# medidor_nao_invasivo.net
KiCad netlist of a schematic drawn in EAGLE
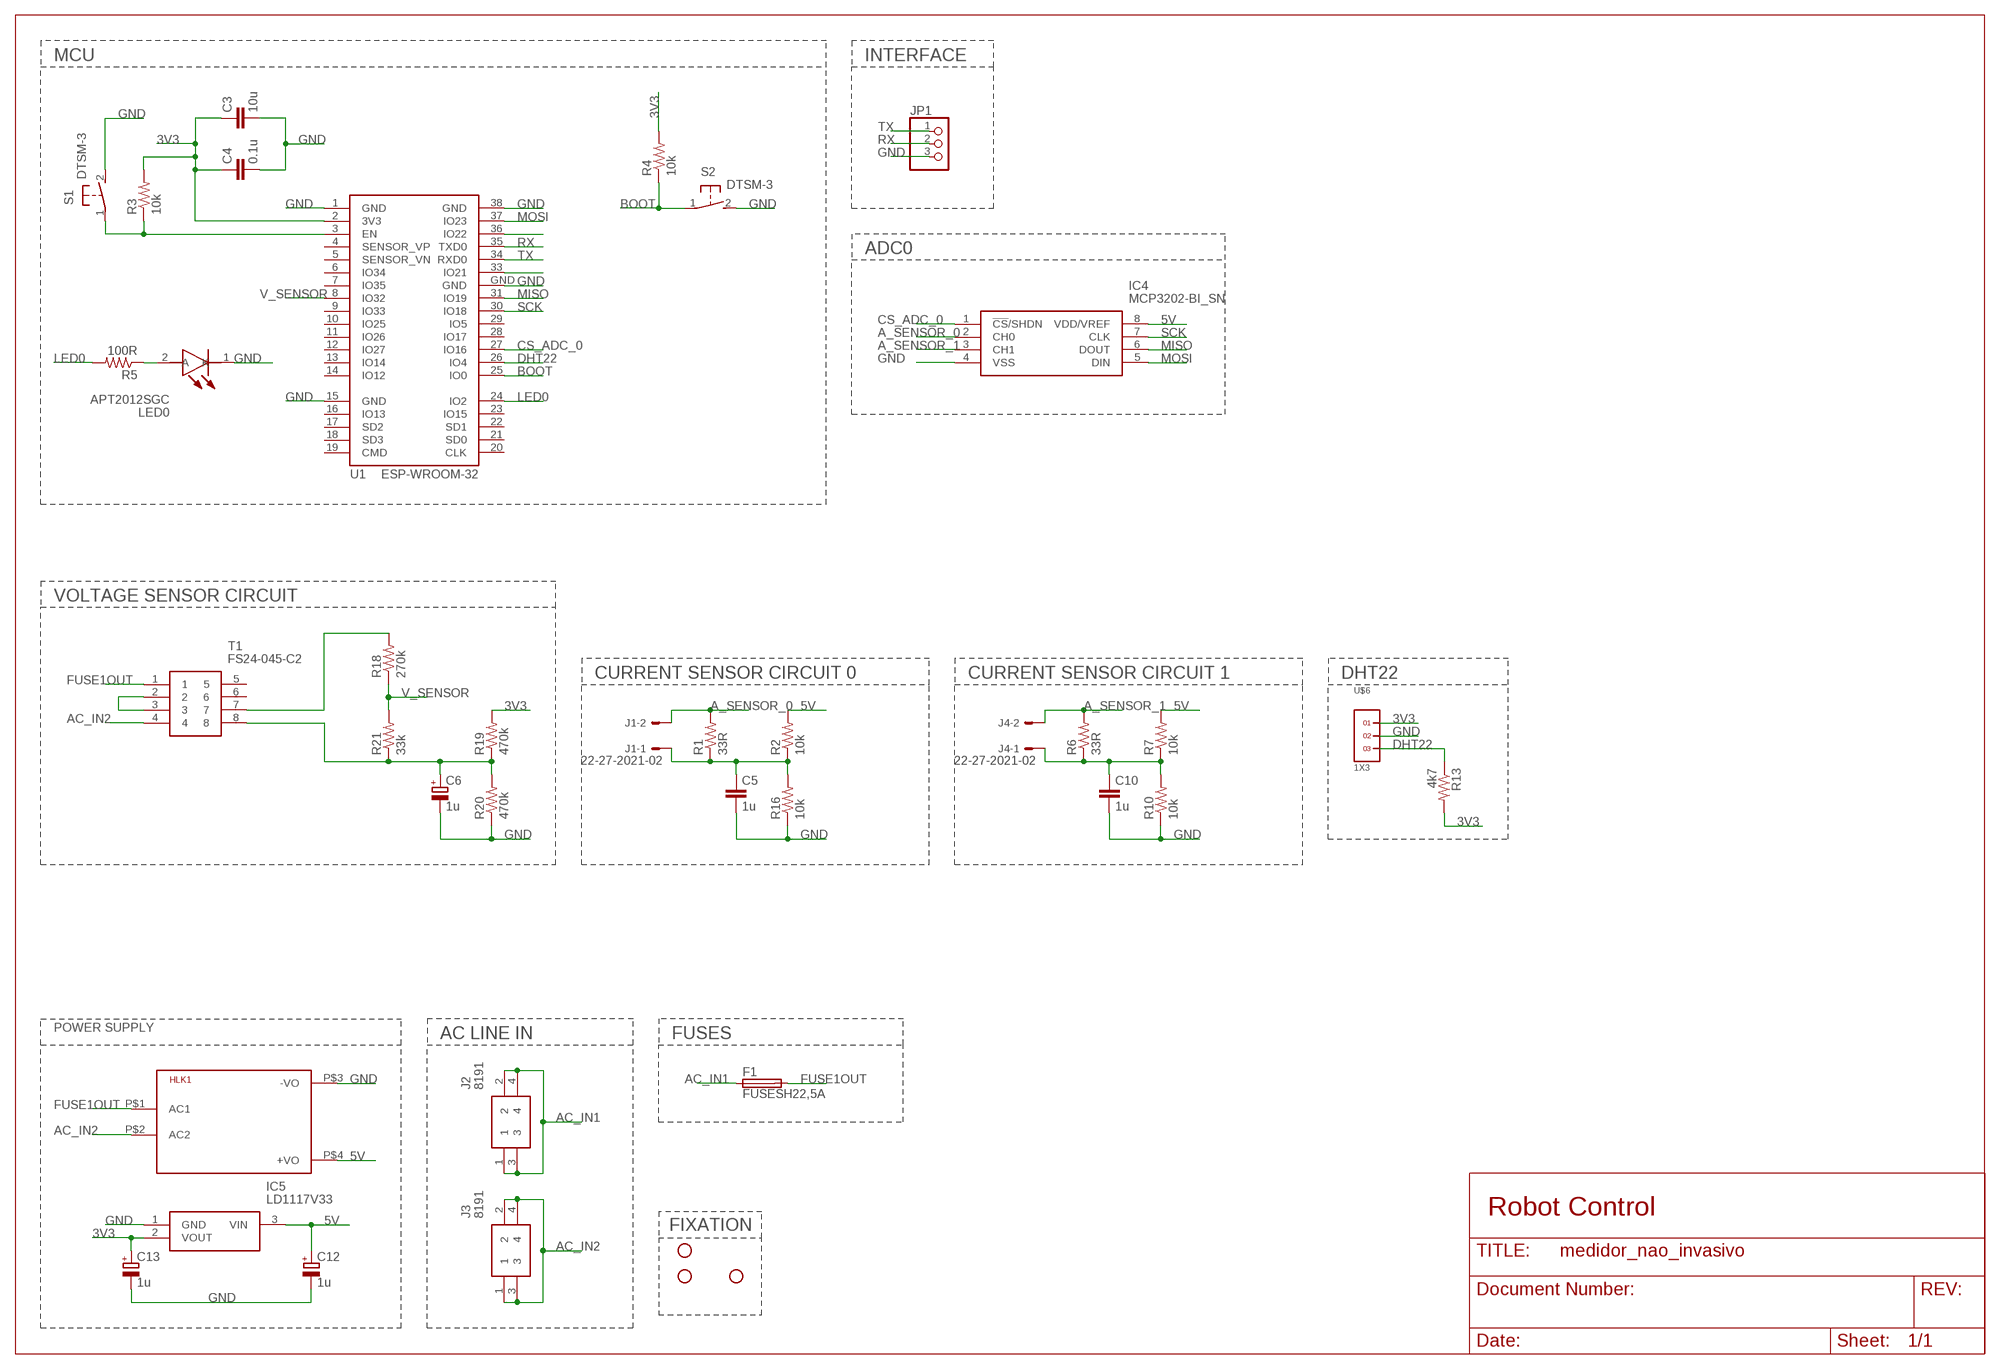
[diagram p0: schematic, sheet 1]

(export (version "E")
  (design (tool "Eeschema 10.0.6"))
  (components
    (comp (ref "C3")
      (value "10u")
      (footprint "eagle-import:C0805")
      (libsource (lib "eagle-import") (part "C-EUC0805"))
    )
    (comp (ref "C4")
      (value "0.1u")
      (footprint "eagle-import:C0805")
      (libsource (lib "eagle-import") (part "C-EUC0805"))
    )
    (comp (ref "C5")
      (value "1u")
      (footprint "eagle-import:C0805")
      (libsource (lib "eagle-import") (part "C-EUC0805"))
    )
    (comp (ref "C6")
      (value "1u")
      (footprint "eagle-import:E1,8-4")
      (libsource (lib "eagle-import") (part "CPOL-EUE1.8-4"))
    )
    (comp (ref "C10")
      (value "1u")
      (footprint "eagle-import:C0805")
      (libsource (lib "eagle-import") (part "C-EUC0805"))
    )
    (comp (ref "C12")
      (value "1u")
      (footprint "eagle-import:E1,8-4")
      (libsource (lib "eagle-import") (part "CPOL-EUE1.8-4"))
    )
    (comp (ref "C13")
      (value "1u")
      (footprint "eagle-import:E1,8-4")
      (libsource (lib "eagle-import") (part "CPOL-EUE1.8-4"))
    )
    (comp (ref "F1")
      (value "FUSESH22,5A")
      (footprint "eagle-import:SH22,5A")
      (libsource (lib "eagle-import") (part "FUSESH22,5A"))
    )
    (comp (ref "HLK1")
      (value "HLK-PM013W")
      (footprint "eagle-import:HLK-PM01")
      (libsource (lib "eagle-import") (part "HLK-PM013W"))
    )
    (comp (ref "IC4")
      (value "MCP3202-BI_SN")
      (footprint "eagle-import:SOIC127P600X175-8N")
      (fields
        (field (name "MANUFACTURER_PART_NUMBER") "MCP3202-BI/SN")
        (field (name "MOUSER_PART_NUMBER") "579-MCP3202BISN")
      )
      (libsource (lib "eagle-import") (part "MCP3202-BI_SN"))
    )
    (comp (ref "IC5")
      (value "LD1117V33")
      (footprint "eagle-import:TO270P460X1020X2008-3P")
      (fields (field (name "MOUSER_PART_NUMBER") "511-LD1117V33"))
      (libsource (lib "eagle-import") (part "LD1117V33"))
    )
    (comp (ref "J1")
      (value "22-27-2021-02")
      (footprint "eagle-import:6410-02")
      (fields (field (name "MF") "MOLEX"))
      (libsource (lib "eagle-import") (part "22-?-0227-2021"))
    )
    (comp (ref "J2")
      (value "8191")
      (footprint "eagle-import:8191")
      (fields (field (name "MOUSER_PART_NUMBER") "534-8191"))
      (libsource (lib "eagle-import") (part "8191"))
    )
    (comp (ref "J3")
      (value "8191")
      (footprint "eagle-import:8191")
      (fields (field (name "MOUSER_PART_NUMBER") "534-8191"))
      (libsource (lib "eagle-import") (part "8191"))
    )
    (comp (ref "J4")
      (value "22-27-2021-02")
      (footprint "eagle-import:6410-02")
      (fields (field (name "MF") "MOLEX"))
      (libsource (lib "eagle-import") (part "22-?-0227-2021"))
    )
    (comp (ref "JP1")
      (value "PINHD-1X3")
      (footprint "eagle-import:1X03")
      (libsource (lib "eagle-import") (part "PINHD-1X3"))
    )
    (comp (ref "LED0")
      (value "APT2012SGC")
      (footprint "eagle-import:LEDC2012X85N")
      (fields (field (name "MOUSER_PART_NUMBER") "604-APT2012SGC"))
      (libsource (lib "eagle-import") (part "APT2012SGC"))
    )
    (comp (ref "R1")
      (value "33R")
      (footprint "eagle-import:R0805")
      (libsource (lib "eagle-import") (part "R-US_R0805"))
    )
    (comp (ref "R2")
      (value "10k")
      (footprint "eagle-import:R0805")
      (libsource (lib "eagle-import") (part "R-US_R0805"))
    )
    (comp (ref "R3")
      (value "10k")
      (footprint "eagle-import:R0805")
      (libsource (lib "eagle-import") (part "R-US_R0805"))
    )
    (comp (ref "R4")
      (value "10k")
      (footprint "eagle-import:R0805")
      (libsource (lib "eagle-import") (part "R-US_R0805"))
    )
    (comp (ref "R5")
      (value "100R")
      (footprint "eagle-import:R0805")
      (libsource (lib "eagle-import") (part "R-US_R0805"))
    )
    (comp (ref "R6")
      (value "33R")
      (footprint "eagle-import:R0805")
      (libsource (lib "eagle-import") (part "R-US_R0805"))
    )
    (comp (ref "R7")
      (value "10k")
      (footprint "eagle-import:R0805")
      (libsource (lib "eagle-import") (part "R-US_R0805"))
    )
    (comp (ref "R10")
      (value "10k")
      (footprint "eagle-import:R0805")
      (libsource (lib "eagle-import") (part "R-US_R0805"))
    )
    (comp (ref "R13")
      (value "4k7")
      (footprint "eagle-import:R0805")
      (libsource (lib "eagle-import") (part "R-US_R0805"))
    )
    (comp (ref "R16")
      (value "10k")
      (footprint "eagle-import:R0805")
      (libsource (lib "eagle-import") (part "R-US_R0805"))
    )
    (comp (ref "R18")
      (value "270k")
      (footprint "eagle-import:AXIAL-0.3-KIT")
      (libsource (lib "eagle-import") (part "RESISTORAXIAL-0.3-KIT"))
    )
    (comp (ref "R19")
      (value "470k")
      (footprint "eagle-import:AXIAL-0.3-KIT")
      (libsource (lib "eagle-import") (part "RESISTORAXIAL-0.3-KIT"))
    )
    (comp (ref "R20")
      (value "470k")
      (footprint "eagle-import:AXIAL-0.3-KIT")
      (libsource (lib "eagle-import") (part "RESISTORAXIAL-0.3-KIT"))
    )
    (comp (ref "R21")
      (value "33k")
      (footprint "eagle-import:AXIAL-0.3-KIT")
      (libsource (lib "eagle-import") (part "RESISTORAXIAL-0.3-KIT"))
    )
    (comp (ref "S1")
      (value "DTSM-3")
      (footprint "eagle-import:DTSM-3")
      (libsource (lib "eagle-import") (part "DTSM-3"))
    )
    (comp (ref "S2")
      (value "DTSM-3")
      (footprint "eagle-import:DTSM-3")
      (libsource (lib "eagle-import") (part "DTSM-3"))
    )
    (comp (ref "STANDOFF1")
      (value "STAND-OFF")
      (footprint "eagle-import:STAND-OFF")
      (libsource (lib "eagle-import") (part "STAND-OFF"))
    )
    (comp (ref "STANDOFF2")
      (value "STAND-OFF")
      (footprint "eagle-import:STAND-OFF")
      (libsource (lib "eagle-import") (part "STAND-OFF"))
    )
    (comp (ref "STANDOFF4")
      (value "STAND-OFF")
      (footprint "eagle-import:STAND-OFF")
      (libsource (lib "eagle-import") (part "STAND-OFF"))
    )
    (comp (ref "T1")
      (value "FS24-045-C2")
      (footprint "eagle-import:FS24045C2")
      (fields (field (name "MOUSER_PART_NUMBER") "553-FS24-045-C2"))
      (libsource (lib "eagle-import") (part "FS24-045-C2"))
    )
    (comp (ref "U$6")
      (value "1X3")
      (footprint "eagle-import:1X3")
      (libsource (lib "eagle-import") (part "1X3"))
    )
    (comp (ref "U1")
      (value "ESP-WROOM-32")
      (footprint "eagle-import:ESP-WROOM-32")
      (libsource (lib "eagle-import") (part "ESP-WROOM-32"))
    )
  )
  (nets
    (net (code "1") (name "/3V3") (class "Default")
      (node (ref "C13") (pin "+") (pinfunction "+_+") (pintype "passive"))
      (node (ref "C3") (pin "1") (pinfunction "1_1") (pintype "passive"))
      (node (ref "C4") (pin "1") (pinfunction "1_1") (pintype "passive"))
      (node (ref "IC5") (pin "2") (pinfunction "VOUT_2") (pintype "output"))
      (node (ref "R13") (pin "2") (pinfunction "2_2") (pintype "passive"))
      (node (ref "R19") (pin "P$2") (pinfunction "2_P$2") (pintype "passive"))
      (node (ref "R3") (pin "2") (pinfunction "2_2") (pintype "passive"))
      (node (ref "R4") (pin "2") (pinfunction "2_2") (pintype "passive"))
      (node (ref "U$6") (pin "1") (pinfunction "1_1") (pintype "bidirectional"))
      (node (ref "U1") (pin "2") (pinfunction "3V3_2") (pintype "power_in"))
    )
    (net (code "2") (name "/5V") (class "Default")
      (node (ref "C12") (pin "+") (pinfunction "+_+") (pintype "passive"))
      (node (ref "HLK1") (pin "P$4") (pinfunction "+VO_P$4") (pintype "bidirectional"))
      (node (ref "IC4") (pin "8") (pinfunction "VDD/VREF_8") (pintype "power_in"))
      (node (ref "IC5") (pin "3") (pinfunction "VIN_3") (pintype "input"))
      (node (ref "R2") (pin "2") (pinfunction "2_2") (pintype "passive"))
      (node (ref "R7") (pin "2") (pinfunction "2_2") (pintype "passive"))
    )
    (net (code "3") (name "/AC_IN1") (class "Default")
      (node (ref "F1") (pin "1") (pinfunction "1_1") (pintype "passive"))
      (node (ref "J2") (pin "1") (pinfunction "1_1") (pintype "bidirectional"))
      (node (ref "J2") (pin "2") (pinfunction "2_2") (pintype "bidirectional"))
      (node (ref "J2") (pin "3") (pinfunction "3_3") (pintype "bidirectional"))
      (node (ref "J2") (pin "4") (pinfunction "4_4") (pintype "bidirectional"))
    )
    (net (code "4") (name "/AC_IN2") (class "Default")
      (node (ref "HLK1") (pin "P$2") (pinfunction "AC2_P$2") (pintype "bidirectional"))
      (node (ref "J3") (pin "1") (pinfunction "1_1") (pintype "bidirectional"))
      (node (ref "J3") (pin "2") (pinfunction "2_2") (pintype "bidirectional"))
      (node (ref "J3") (pin "3") (pinfunction "3_3") (pintype "bidirectional"))
      (node (ref "J3") (pin "4") (pinfunction "4_4") (pintype "bidirectional"))
      (node (ref "T1") (pin "4") (pinfunction "4_4") (pintype "bidirectional"))
    )
    (net (code "5") (name "/A_SENSOR_0") (class "Default")
      (node (ref "IC4") (pin "2") (pinfunction "CH0_2") (pintype "bidirectional"))
      (node (ref "J1") (pin "2") (pinfunction "S_2") (pintype "passive"))
      (node (ref "R1") (pin "2") (pinfunction "2_2") (pintype "passive"))
    )
    (net (code "6") (name "/A_SENSOR_1") (class "Default")
      (node (ref "IC4") (pin "3") (pinfunction "CH1_3") (pintype "bidirectional"))
      (node (ref "J4") (pin "2") (pinfunction "S_2") (pintype "passive"))
      (node (ref "R6") (pin "2") (pinfunction "2_2") (pintype "passive"))
    )
    (net (code "7") (name "/BOOT") (class "Default")
      (node (ref "R4") (pin "1") (pinfunction "1_1") (pintype "passive"))
      (node (ref "S2") (pin "1") (pinfunction "1_1") (pintype "passive"))
      (node (ref "U1") (pin "25") (pinfunction "IO0_25") (pintype "bidirectional"))
    )
    (net (code "8") (name "/CS_ADC_0") (class "Default")
      (node (ref "IC4") (pin "1") (pinfunction "~{CS}/SHDN_1") (pintype "input"))
      (node (ref "U1") (pin "27") (pinfunction "IO16_27") (pintype "bidirectional"))
    )
    (net (code "9") (name "/DHT22") (class "Default")
      (node (ref "R13") (pin "1") (pinfunction "1_1") (pintype "passive"))
      (node (ref "U$6") (pin "3") (pinfunction "3_3") (pintype "bidirectional"))
      (node (ref "U1") (pin "26") (pinfunction "IO4_26") (pintype "bidirectional"))
    )
    (net (code "10") (name "/FUSE1OUT") (class "Default")
      (node (ref "F1") (pin "2") (pinfunction "2_2") (pintype "passive"))
      (node (ref "HLK1") (pin "P$1") (pinfunction "AC1_P$1") (pintype "bidirectional"))
      (node (ref "T1") (pin "1") (pinfunction "1_1") (pintype "bidirectional"))
    )
    (net (code "11") (name "/GND") (class "Default")
      (node (ref "C10") (pin "2") (pinfunction "2_2") (pintype "passive"))
      (node (ref "C12") (pin "-") (pinfunction "-_-") (pintype "passive"))
      (node (ref "C13") (pin "-") (pinfunction "-_-") (pintype "passive"))
      (node (ref "C3") (pin "2") (pinfunction "2_2") (pintype "passive"))
      (node (ref "C4") (pin "2") (pinfunction "2_2") (pintype "passive"))
      (node (ref "C5") (pin "2") (pinfunction "2_2") (pintype "passive"))
      (node (ref "C6") (pin "-") (pinfunction "-_-") (pintype "passive"))
      (node (ref "HLK1") (pin "P$3") (pinfunction "-VO_P$3") (pintype "bidirectional"))
      (node (ref "IC4") (pin "4") (pinfunction "VSS_4") (pintype "power_in"))
      (node (ref "IC5") (pin "1") (pinfunction "GND_1") (pintype "power_in"))
      (node (ref "JP1") (pin "3") (pinfunction "3_3") (pintype "passive"))
      (node (ref "LED0") (pin "1") (pinfunction "K_1") (pintype "bidirectional"))
      (node (ref "R10") (pin "1") (pinfunction "1_1") (pintype "passive"))
      (node (ref "R16") (pin "1") (pinfunction "1_1") (pintype "passive"))
      (node (ref "R20") (pin "P$1") (pinfunction "1_P$1") (pintype "passive"))
      (node (ref "S1") (pin "2") (pinfunction "2_2") (pintype "passive"))
      (node (ref "S2") (pin "2") (pinfunction "2_2") (pintype "passive"))
      (node (ref "U$6") (pin "2") (pinfunction "2_2") (pintype "bidirectional"))
      (node (ref "U1") (pin "1") (pinfunction "GND_1") (pintype "power_in"))
      (node (ref "U1") (pin "15") (pinfunction "GND_15") (pintype "power_in"))
      (node (ref "U1") (pin "38") (pinfunction "GND_38") (pintype "power_in"))
      (node (ref "U1") (pin "GND") (pinfunction "GND_GND") (pintype "power_in"))
    )
    (net (code "12") (name "/LED0") (class "Default")
      (node (ref "R5") (pin "2") (pinfunction "2_2") (pintype "passive"))
      (node (ref "U1") (pin "24") (pinfunction "IO2_24") (pintype "bidirectional"))
    )
    (net (code "13") (name "/MISO") (class "Default")
      (node (ref "IC4") (pin "6") (pinfunction "DOUT_6") (pintype "output"))
      (node (ref "U1") (pin "31") (pinfunction "IO19_31") (pintype "bidirectional"))
    )
    (net (code "14") (name "/MOSI") (class "Default")
      (node (ref "IC4") (pin "5") (pinfunction "DIN_5") (pintype "input"))
      (node (ref "U1") (pin "37") (pinfunction "IO23_37") (pintype "bidirectional"))
    )
    (net (code "15") (name "/RX") (class "Default")
      (node (ref "JP1") (pin "2") (pinfunction "2_2") (pintype "passive"))
      (node (ref "U1") (pin "35") (pinfunction "TXD0_35") (pintype "bidirectional"))
    )
    (net (code "16") (name "/SCK") (class "Default")
      (node (ref "IC4") (pin "7") (pinfunction "CLK_7") (pintype "input"))
      (node (ref "U1") (pin "30") (pinfunction "IO18_30") (pintype "bidirectional"))
    )
    (net (code "17") (name "/TX") (class "Default")
      (node (ref "JP1") (pin "1") (pinfunction "1_1") (pintype "passive"))
      (node (ref "U1") (pin "34") (pinfunction "RXD0_34") (pintype "bidirectional"))
    )
    (net (code "18") (name "/V_SENSOR") (class "Default")
      (node (ref "R18") (pin "P$1") (pinfunction "1_P$1") (pintype "passive"))
      (node (ref "R21") (pin "P$2") (pinfunction "2_P$2") (pintype "passive"))
      (node (ref "U1") (pin "8") (pinfunction "IO32_8") (pintype "bidirectional"))
    )
    (net (code "19") (name "Net-(J1A-S)") (class "Default")
      (node (ref "C5") (pin "1") (pinfunction "1_1") (pintype "passive"))
      (node (ref "J1") (pin "1") (pinfunction "S_1") (pintype "passive"))
      (node (ref "R1") (pin "1") (pinfunction "1_1") (pintype "passive"))
      (node (ref "R16") (pin "2") (pinfunction "2_2") (pintype "passive"))
      (node (ref "R2") (pin "1") (pinfunction "1_1") (pintype "passive"))
    )
    (net (code "20") (name "Net-(J4A-S)") (class "Default")
      (node (ref "C10") (pin "1") (pinfunction "1_1") (pintype "passive"))
      (node (ref "J4") (pin "1") (pinfunction "S_1") (pintype "passive"))
      (node (ref "R10") (pin "2") (pinfunction "2_2") (pintype "passive"))
      (node (ref "R6") (pin "1") (pinfunction "1_1") (pintype "passive"))
      (node (ref "R7") (pin "1") (pinfunction "1_1") (pintype "passive"))
    )
    (net (code "21") (name "Net-(LED0-A)") (class "Default")
      (node (ref "LED0") (pin "2") (pinfunction "A_2") (pintype "bidirectional"))
      (node (ref "R5") (pin "1") (pinfunction "1_1") (pintype "passive"))
    )
    (net (code "22") (name "Net-(R18-2)") (class "Default")
      (node (ref "R18") (pin "P$2") (pinfunction "2_P$2") (pintype "passive"))
      (node (ref "T1") (pin "7") (pinfunction "7_7") (pintype "bidirectional"))
    )
    (net (code "23") (name "Net-(R19-1)") (class "Default")
      (node (ref "C6") (pin "+") (pinfunction "+_+") (pintype "passive"))
      (node (ref "R19") (pin "P$1") (pinfunction "1_P$1") (pintype "passive"))
      (node (ref "R20") (pin "P$2") (pinfunction "2_P$2") (pintype "passive"))
      (node (ref "R21") (pin "P$1") (pinfunction "1_P$1") (pintype "passive"))
      (node (ref "T1") (pin "8") (pinfunction "8_8") (pintype "bidirectional"))
    )
    (net (code "24") (name "Net-(T1-Pad2)") (class "Default")
      (node (ref "T1") (pin "2") (pinfunction "2_2") (pintype "bidirectional"))
      (node (ref "T1") (pin "3") (pinfunction "3_3") (pintype "bidirectional"))
    )
    (net (code "25") (name "Net-(U1-EN)") (class "Default")
      (node (ref "R3") (pin "1") (pinfunction "1_1") (pintype "passive"))
      (node (ref "S1") (pin "1") (pinfunction "1_1") (pintype "passive"))
      (node (ref "U1") (pin "3") (pinfunction "EN_3") (pintype "input"))
    )
    (net (code "26") (name "unconnected-(T1-Pad5)") (class "Default")
      (node (ref "T1") (pin "5") (pinfunction "5_5") (pintype "bidirectional"))
    )
    (net (code "27") (name "unconnected-(T1-Pad6)") (class "Default")
      (node (ref "T1") (pin "6") (pinfunction "6_6") (pintype "bidirectional"))
    )
    (net (code "28") (name "unconnected-(U1-CLK-Pad20)") (class "Default")
      (node (ref "U1") (pin "20") (pinfunction "CLK_20") (pintype "bidirectional"))
    )
    (net (code "29") (name "unconnected-(U1-CMD-Pad19)") (class "Default")
      (node (ref "U1") (pin "19") (pinfunction "CMD_19") (pintype "bidirectional"))
    )
    (net (code "30") (name "unconnected-(U1-IO5-Pad29)") (class "Default")
      (node (ref "U1") (pin "29") (pinfunction "IO5_29") (pintype "bidirectional"))
    )
    (net (code "31") (name "unconnected-(U1-IO12-Pad14)") (class "Default")
      (node (ref "U1") (pin "14") (pinfunction "IO12_14") (pintype "bidirectional"))
    )
    (net (code "32") (name "unconnected-(U1-IO13-Pad16)") (class "Default")
      (node (ref "U1") (pin "16") (pinfunction "IO13_16") (pintype "bidirectional"))
    )
    (net (code "33") (name "unconnected-(U1-IO14-Pad13)") (class "Default")
      (node (ref "U1") (pin "13") (pinfunction "IO14_13") (pintype "bidirectional"))
    )
    (net (code "34") (name "unconnected-(U1-IO15-Pad23)") (class "Default")
      (node (ref "U1") (pin "23") (pinfunction "IO15_23") (pintype "bidirectional"))
    )
    (net (code "35") (name "unconnected-(U1-IO17-Pad28)") (class "Default")
      (node (ref "U1") (pin "28") (pinfunction "IO17_28") (pintype "bidirectional"))
    )
    (net (code "36") (name "unconnected-(U1-IO21-Pad33)") (class "Default")
      (node (ref "U1") (pin "33") (pinfunction "IO21_33") (pintype "bidirectional"))
    )
    (net (code "37") (name "unconnected-(U1-IO22-Pad36)") (class "Default")
      (node (ref "U1") (pin "36") (pinfunction "IO22_36") (pintype "bidirectional"))
    )
    (net (code "38") (name "unconnected-(U1-IO25-Pad10)") (class "Default")
      (node (ref "U1") (pin "10") (pinfunction "IO25_10") (pintype "bidirectional"))
    )
    (net (code "39") (name "unconnected-(U1-IO26-Pad11)") (class "Default")
      (node (ref "U1") (pin "11") (pinfunction "IO26_11") (pintype "bidirectional"))
    )
    (net (code "40") (name "unconnected-(U1-IO27-Pad12)") (class "Default")
      (node (ref "U1") (pin "12") (pinfunction "IO27_12") (pintype "bidirectional"))
    )
    (net (code "41") (name "unconnected-(U1-IO33-Pad9)") (class "Default")
      (node (ref "U1") (pin "9") (pinfunction "IO33_9") (pintype "bidirectional"))
    )
    (net (code "42") (name "unconnected-(U1-IO34-Pad6)") (class "Default")
      (node (ref "U1") (pin "6") (pinfunction "IO34_6") (pintype "bidirectional"))
    )
    (net (code "43") (name "unconnected-(U1-IO35-Pad7)") (class "Default")
      (node (ref "U1") (pin "7") (pinfunction "IO35_7") (pintype "bidirectional"))
    )
    (net (code "44") (name "unconnected-(U1-SD0-Pad21)") (class "Default")
      (node (ref "U1") (pin "21") (pinfunction "SD0_21") (pintype "bidirectional"))
    )
    (net (code "45") (name "unconnected-(U1-SD1-Pad22)") (class "Default")
      (node (ref "U1") (pin "22") (pinfunction "SD1_22") (pintype "bidirectional"))
    )
    (net (code "46") (name "unconnected-(U1-SD2-Pad17)") (class "Default")
      (node (ref "U1") (pin "17") (pinfunction "SD2_17") (pintype "bidirectional"))
    )
    (net (code "47") (name "unconnected-(U1-SD3-Pad18)") (class "Default")
      (node (ref "U1") (pin "18") (pinfunction "SD3_18") (pintype "bidirectional"))
    )
    (net (code "48") (name "unconnected-(U1-SENSOR_VN-Pad5)") (class "Default")
      (node (ref "U1") (pin "5") (pinfunction "SENSOR_VN_5") (pintype "bidirectional"))
    )
    (net (code "49") (name "unconnected-(U1-SENSOR_VP-Pad4)") (class "Default")
      (node (ref "U1") (pin "4") (pinfunction "SENSOR_VP_4") (pintype "bidirectional"))
    )
  )
)
